# PMP30528_RevB.net
KiCad netlist of a schematic drawn in Altium Designer
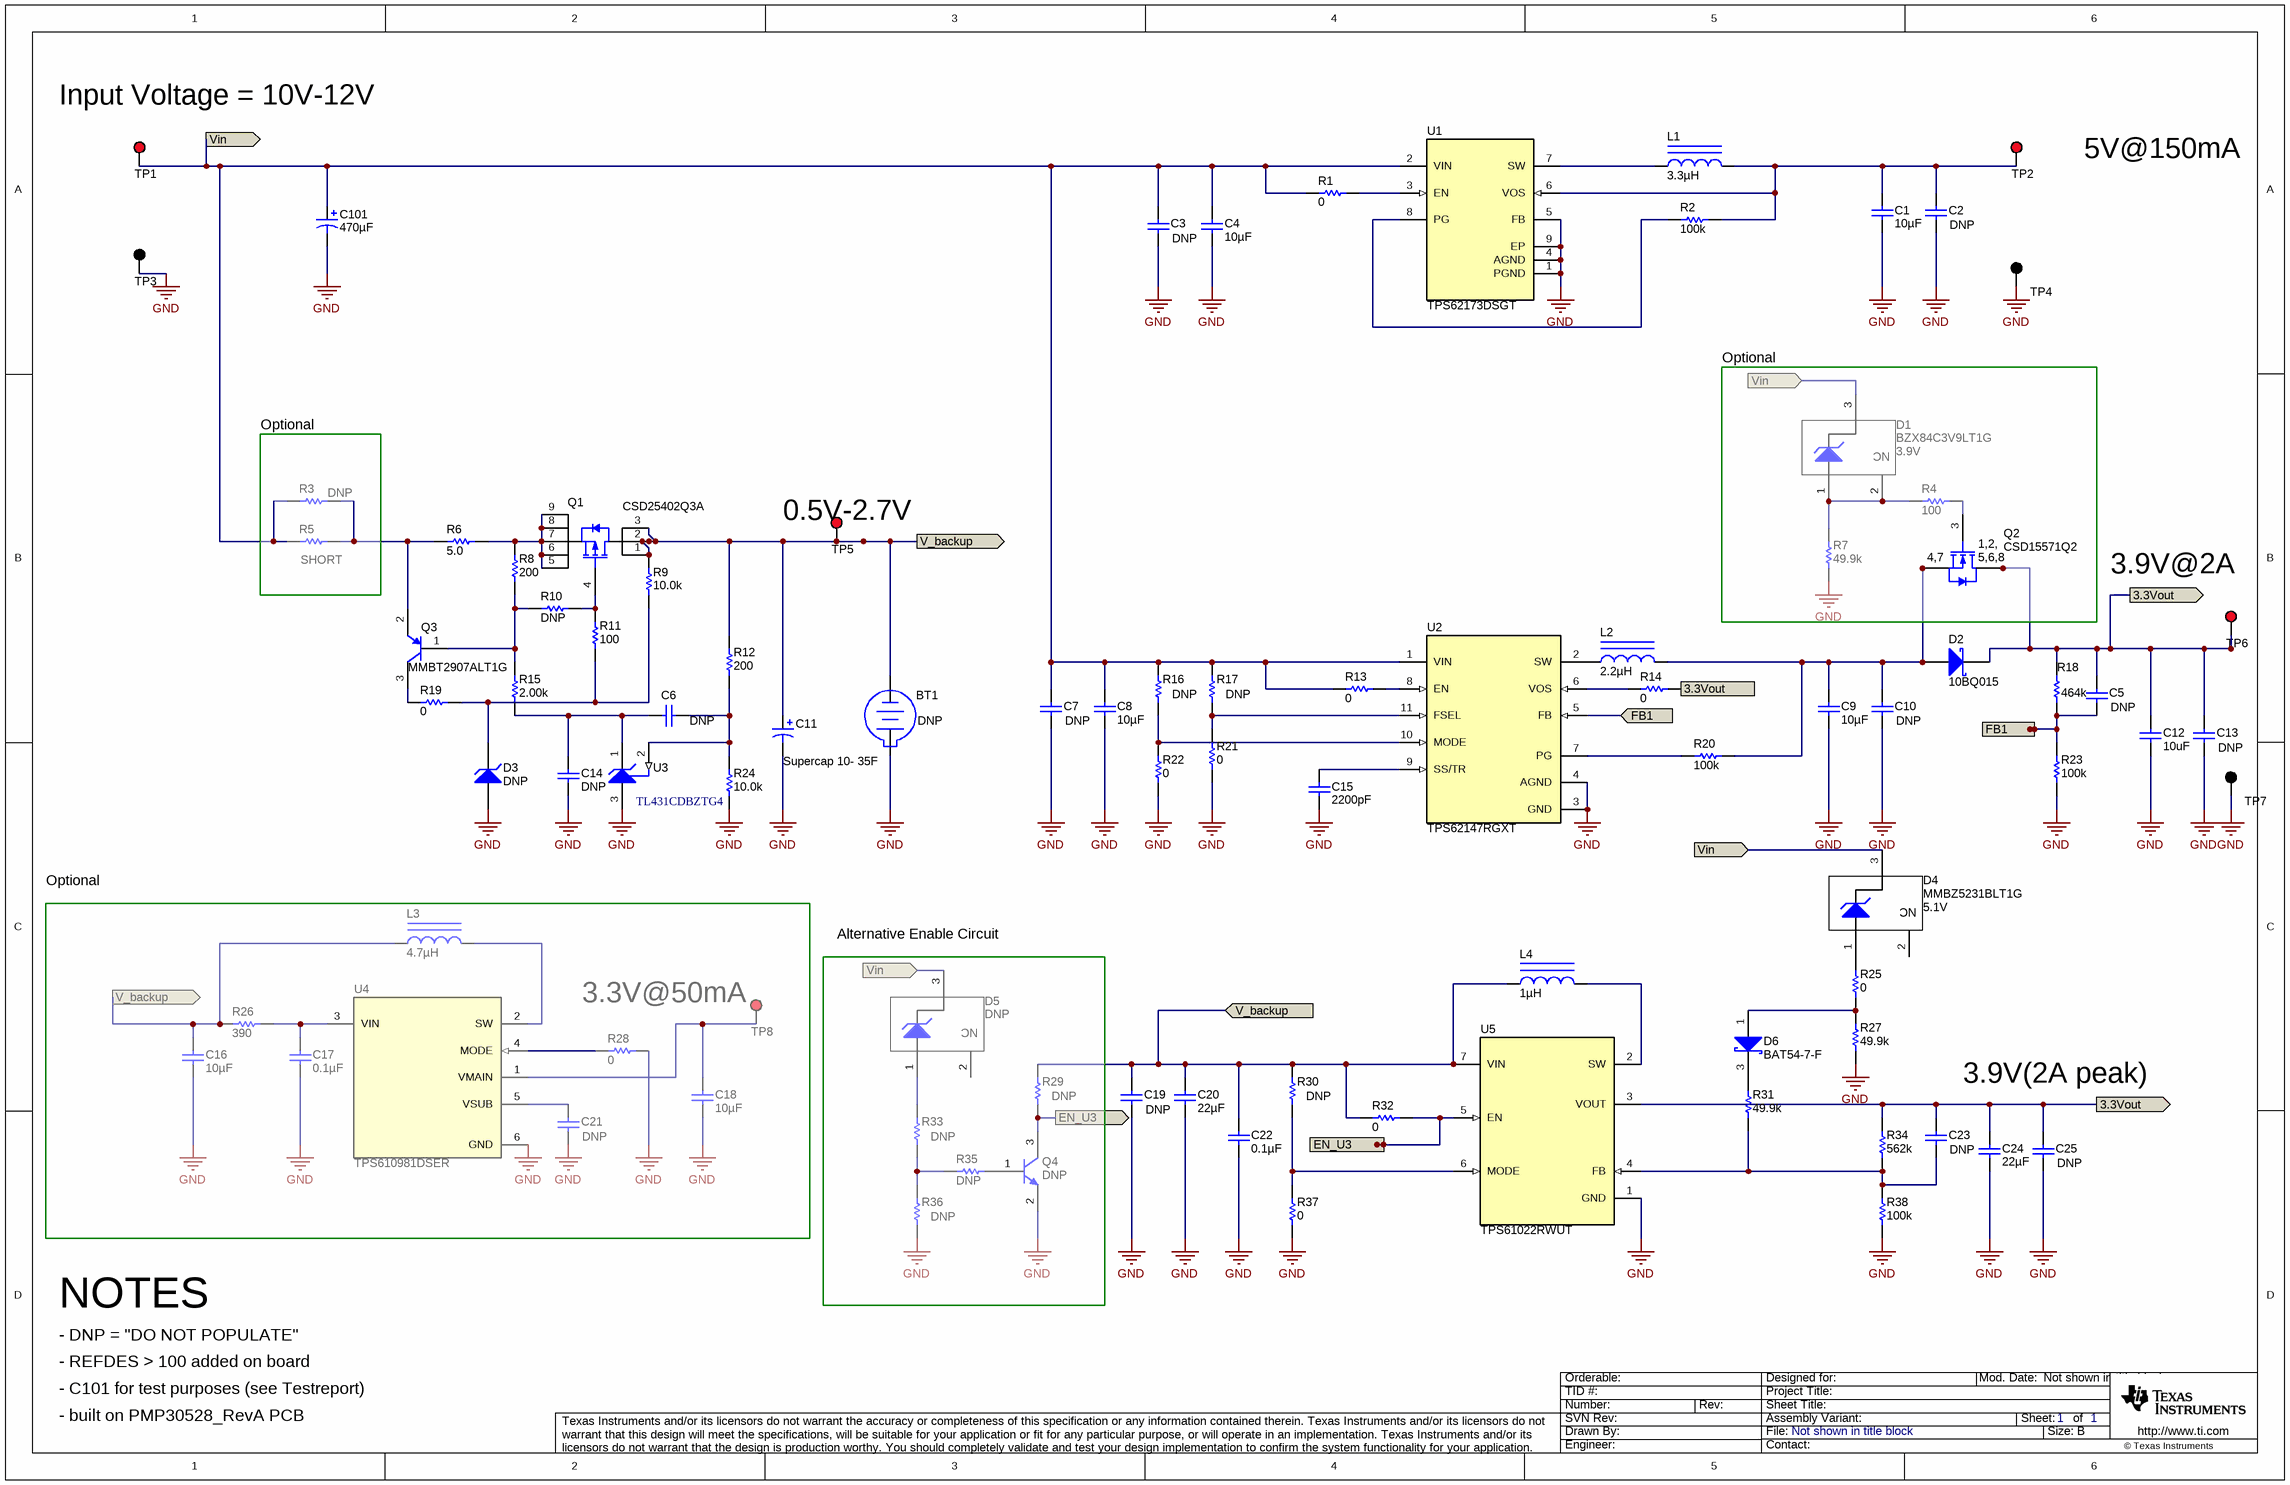
[diagram p0: PMP30528_RevB.SchDoc]

(export (version "E")
  (design (tool "Eeschema 10.0.6"))
  (components
    (comp (ref "BT1")
      (value "BU2032SM-BT-GTR")
      (footprint "MPD_BU2032SM-BT-GTR")
      (description "HOLDER CR2032 GOLD LEADS SMD")
      (fields (field (name "MANUFACTURER") "Memory Protection Devices") (field (name "PARTNUMBER") "DNP"))
      (libsource (lib "Altium Vault - TI") (part "BatteryHolder_Coin"))
    )
    (comp (ref "C1")
      (value "GRM21BR71A106KE51K")
      (footprint "0805_HV")
      (description "CAP, CERM, 10 µF, 10 V,+/- 10%, X7R, 0805")
      (fields
        (field (name "VALUEDISPLAYED") "10µF")
        (field (name "MANUFACTURER") "MuRata")
        (field (name "PUBLISHER") "Texas Instruments")
      )
      (libsource (lib "Capacitor_Ceramic") (part "GRM21BR71A106KE51K"))
    )
    (comp (ref "C2")
      (value "DNP")
      (footprint "0805")
      (description "CAP, CERM, xxxF, xxV, [TempCo], xx%, [PackageReference]")
      (fields
        (field (name "MANUFACTURER") "Used in BOM report")
        (field (name "PUBLISHER") "Texas Instruments")
      )
      (libsource (lib "MiscParts") (part "Capacitor"))
    )
    (comp (ref "C3")
      (value "DNP")
      (footprint "0805")
      (description "CAP, CERM, xxxF, xxV, [TempCo], xx%, [PackageReference]")
      (fields
        (field (name "MANUFACTURER") "Used in BOM report")
        (field (name "PUBLISHER") "Texas Instruments")
      )
      (libsource (lib "MiscParts") (part "Capacitor"))
    )
    (comp (ref "C4")
      (value "GRM21BZ71E106KE15L")
      (footprint "0805_HV")
      (description "CAP, CERM, 10 µF, 25 V,+/- 10%, X7R, 0805")
      (fields
        (field (name "VALUEDISPLAYED") "10µF")
        (field (name "MANUFACTURER") "MuRata")
        (field (name "PUBLISHER") "Texas Instruments")
      )
      (libsource (lib "Capacitor_Ceramic") (part "GRM21BZ71E106KE15L"))
    )
    (comp (ref "C5")
      (value "DNP")
      (footprint "0603")
      (description "CAP, CERM, xxxF, xxV, [TempCo], xx%, [PackageReference]")
      (fields
        (field (name "MANUFACTURER") "Used in BOM report")
        (field (name "PUBLISHER") "Texas Instruments")
      )
      (libsource (lib "MiscParts") (part "Capacitor"))
    )
    (comp (ref "C6")
      (value "DNP")
      (footprint "0805")
      (description "CAP, CERM, xxxF, xxV, [TempCo], xx%, [PackageReference]")
      (fields
        (field (name "MANUFACTURER") "Used in BOM report")
        (field (name "PUBLISHER") "Texas Instruments")
      )
      (libsource (lib "MiscParts") (part "Capacitor"))
    )
    (comp (ref "C7")
      (value "DNP")
      (footprint "0805")
      (description "CAP, CERM, xxxF, xxV, [TempCo], xx%, [PackageReference]")
      (fields
        (field (name "MANUFACTURER") "Used in BOM report")
        (field (name "PUBLISHER") "Texas Instruments")
      )
      (libsource (lib "MiscParts") (part "Capacitor"))
    )
    (comp (ref "C8")
      (value "GRM21BZ71E106KE15L")
      (footprint "0805")
      (description "CAP, CERM, 10 µF, 25 V,+/- 10%, X7R, 0805")
      (fields
        (field (name "VALUEDISPLAYED") "10µF")
        (field (name "MANUFACTURER") "MuRata")
        (field (name "PUBLISHER") "Texas Instruments")
      )
      (libsource (lib "Capacitor_Ceramic") (part "GRM21BZ71E106KE15L"))
    )
    (comp (ref "C9")
      (value "GRM31CR70J106KA01L")
      (footprint "1206_180")
      (description "CAP, CERM, 10 µF, 6.3 V,+/- 10%, X7R, 1206")
      (fields
        (field (name "VALUEDISPLAYED") "10µF")
        (field (name "MANUFACTURER") "MuRata")
        (field (name "PUBLISHER") "Texas Instruments")
      )
      (libsource (lib "Capacitor_Ceramic") (part "GRM31CR70J106KA01L"))
    )
    (comp (ref "C10")
      (value "DNP")
      (footprint "1206")
      (description "CAP, CERM, xxxF, xxV, [TempCo], xx%, [PackageReference]")
      (fields
        (field (name "MANUFACTURER") "Used in BOM report")
        (field (name "PUBLISHER") "Texas Instruments")
      )
      (libsource (lib "MiscParts") (part "Capacitor"))
    )
    (comp (ref "C11")
      (value "HV1625-2R7256-R")
      (footprint "HV_1600x2840")
      (description "CAP, Electric Double Layer, 25000000 µF, 2.7 V,+30/-10%, 0.027 ohm, TH")
      (fields (field (name "MANUFACTURER") "Eaton") (field (name "PARTNUMBER") "Supercap 10- 35F"))
      (libsource (lib "Altium Vault - TI") (part "CMP-0084049-1"))
    )
    (comp (ref "C12")
      (value "10uF")
      (footprint "1206")
      (description "CAP, CERM, 10 uF, 6.3 V, +/- 10%, X7R, 1206")
      (fields
        (field (name "MANUFACTURER") "TDK")
        (field (name "Comment") "C3216X7R1A106K085AC")
        (field (name "PUBLISHER") "Texas Instruments")
      )
      (libsource (lib "Altium Vault - TI") (part "CMP-0008687-2"))
    )
    (comp (ref "C13")
      (value "C3216X7R1A106K085AC")
      (footprint "1206")
      (description "CAP, CERM, 1206")
      (fields
        (field (name "MANUFACTURER") "TDK")
        (field (name "PARTNUMBER") "DNP")
        (field (name "PUBLISHER") "Texas Instruments")
      )
      (libsource (lib "Altium Vault - TI") (part "CMP-0008687-2"))
    )
    (comp (ref "C14")
      (value "DNP")
      (footprint "0805")
      (description "CAP, CERM, xxxF, xxV, [TempCo], xx%, [PackageReference]")
      (fields
        (field (name "MANUFACTURER") "Used in BOM report")
        (field (name "PUBLISHER") "Texas Instruments")
      )
      (libsource (lib "MiscParts") (part "Capacitor"))
    )
    (comp (ref "C15")
      (value "C0603X222K5RACTU")
      (footprint "0603")
      (description "CAP, CERM, 2200 pF, 50 V,+/- 10%, X7R, 0603")
      (fields
        (field (name "VALUEDISPLAYED") "2200pF")
        (field (name "MANUFACTURER") "Kemet")
        (field (name "PUBLISHER") "Texas Instruments")
      )
      (libsource (lib "Capacitor_Ceramic") (part "C0603X222K5RACTU"))
    )
    (comp (ref "C16")
      (value "GRM21BR70J106KE76L")
      (footprint "0805_HV")
      (description "CAP, CERM, 10 µF, 6.3 V,+/- 10%, X7R, 0805")
      (fields
        (field (name "VALUEDISPLAYED") "10µF")
        (field (name "MANUFACTURER") "MuRata")
        (field (name "PUBLISHER") "Texas Instruments")
      )
      (libsource (lib "Capacitor_Ceramic") (part "GRM21BR70J106KE76L"))
    )
    (comp (ref "C17")
      (value "GRM21BR71H104KA01L")
      (footprint "0805_HV")
      (description "CAP, CERM, 0.1 µF, 50 V,+/- 10%, X7R, 0805")
      (fields
        (field (name "VALUEDISPLAYED") "0.1µF")
        (field (name "MANUFACTURER") "MuRata")
        (field (name "PUBLISHER") "Texas Instruments")
      )
      (libsource (lib "Capacitor_Ceramic") (part "GRM21BR71H104KA01L"))
    )
    (comp (ref "C18")
      (value "GRM21BR70J106KE76L")
      (footprint "0805_HV")
      (description "CAP, CERM, 10 µF, 6.3 V,+/- 10%, X7R, 0805")
      (fields
        (field (name "VALUEDISPLAYED") "10µF")
        (field (name "MANUFACTURER") "MuRata")
        (field (name "PUBLISHER") "Texas Instruments")
      )
      (libsource (lib "Capacitor_Ceramic") (part "GRM21BR70J106KE76L"))
    )
    (comp (ref "C19")
      (value "DNP")
      (footprint "0805")
      (description "CAP, CERM, xxxF, xxV, [TempCo], xx%, [PackageReference]")
      (fields
        (field (name "MANUFACTURER") "Used in BOM report")
        (field (name "PUBLISHER") "Texas Instruments")
      )
      (libsource (lib "MiscParts") (part "Capacitor"))
    )
    (comp (ref "C20")
      (value "GRM31CR70J226KE19L")
      (footprint "1206_180")
      (description "CAP, CERM, 22 µF, 6.3 V,+/- 10%, X7R, 1206")
      (fields
        (field (name "VALUEDISPLAYED") "22µF")
        (field (name "MANUFACTURER") "MuRata")
        (field (name "PUBLISHER") "Texas Instruments")
      )
      (libsource (lib "Capacitor_Ceramic") (part "GRM31CR70J226KE19L"))
    )
    (comp (ref "C21")
      (value "DNP")
      (footprint "0805")
      (description "CAP, CERM, xxxF, xxV, [TempCo], xx%, [PackageReference]")
      (fields
        (field (name "MANUFACTURER") "Used in BOM report")
        (field (name "PUBLISHER") "Texas Instruments")
      )
      (libsource (lib "MiscParts") (part "Capacitor"))
    )
    (comp (ref "C22")
      (value "GRM188R71H104KA93D")
      (footprint "0603")
      (description "CAP, CERM, 0.1 µF, 50 V,+/- 10%, X7R, 0603")
      (fields
        (field (name "VALUEDISPLAYED") "0.1µF")
        (field (name "MANUFACTURER") "MuRata")
        (field (name "PUBLISHER") "Texas Instruments")
      )
      (libsource (lib "Capacitor_Ceramic") (part "GRM188R71H104KA93D"))
    )
    (comp (ref "C23")
      (value "DNP")
      (footprint "0603")
      (description "CAP, CERM, xxxF, xxV, [TempCo], xx%, [PackageReference]")
      (fields
        (field (name "MANUFACTURER") "Used in BOM report")
        (field (name "PUBLISHER") "Texas Instruments")
      )
      (libsource (lib "MiscParts") (part "Capacitor"))
    )
    (comp (ref "C24")
      (value "GRM31CR71A226ME15L")
      (footprint "1206_180")
      (description "CAP, CERM, 22 µF, 10 V,+/- 20%, X7R, 1206")
      (fields
        (field (name "VALUEDISPLAYED") "22µF")
        (field (name "MANUFACTURER") "MuRata")
        (field (name "PUBLISHER") "Texas Instruments")
      )
      (libsource (lib "Capacitor_Ceramic") (part "GRM31CR71A226ME15L"))
    )
    (comp (ref "C25")
      (value "DNP")
      (footprint "1206")
      (description "CAP, CERM, xxxF, xxV, [TempCo], xx%, [PackageReference]")
      (fields
        (field (name "MANUFACTURER") "Used in BOM report")
        (field (name "PUBLISHER") "Texas Instruments")
      )
      (libsource (lib "MiscParts") (part "Capacitor"))
    )
    (comp (ref "C101")
      (value "EKZE350ELL471MJ20S")
      (footprint "Chemi-Con_1000x2000")
      (description "CAP, AL, 470 µF, 35 V, +/- 20%, TH")
      (fields
        (field (name "VALUEDISPLAYED") "470µF")
        (field (name "MANUFACTURER") "Chemi-Con")
        (field (name "PUBLISHER") "Texas Instruments")
      )
      (libsource (lib "Capacitor_Aluminum") (part "EKZE350ELL471MJ20S"))
    )
    (comp (ref "D1")
      (value "BZX84C3V9LT1G")
      (footprint "SOT-23")
      (description "Diode, Zener, 3.9 V, 225 mW, SOT-23")
      (fields
        (field (name "MANUFACTURER") "ON Semiconductor")
        (field (name "ALTIUM_VALUE") "3.9V")
        (field (name "PUBLISHER") "Texas Instruments")
      )
      (libsource (lib "ZenerDiodes") (part "BZX84C3V9LT1G"))
    )
    (comp (ref "D2")
      (value "10BQ015")
      (footprint "SMB")
      (description "Diode, Schottky, 15 V, 1 A, SMB")
      (fields
        (field (name "MANUFACTURER") "Vishay-Semiconductor")
        (field (name "PUBLISHER") "Texas Instruments")
      )
      (libsource (lib "Diode") (part "VS-10BQ030HM3/5BT"))
    )
    (comp (ref "D3")
      (value "DNP")
      (footprint "SOD-523")
      (description "Diode, Zener")
      (fields
        (field (name "MANUFACTURER") "Diodes Inc.")
        (field (name "SYMBOLCREATOR") "a0412235")
        (field (name "PUBLISHER") "Texas Instruments")
      )
      (libsource (lib "ZenerDiodes") (part "BZT52C2V7T-7"))
    )
    (comp (ref "D4")
      (value "MMBZ5231BLT1G")
      (footprint "SOT-23")
      (description "Diode, Zener, 5.1 V, 225 mW, SOT-23")
      (fields
        (field (name "MANUFACTURER") "ON Semiconductor")
        (field (name "ALTIUM_VALUE") "5.1V")
        (field (name "PUBLISHER") "Texas Instruments")
      )
      (libsource (lib "ZenerDiodes") (part "MMBZ5231BLT1G"))
    )
    (comp (ref "D5")
      (value "DNP")
      (footprint "SOT-23")
      (description "Diode, Zener")
      (fields (field (name "MANUFACTURER") "ON Semiconductor") (field (name "PUBLISHER") "Texas Instruments"))
      (libsource (lib "ZenerDiodes") (part "MMBZ5231BLT1G"))
    )
    (comp (ref "D6")
      (value "BAT54-7-F")
      (footprint "SOT-23")
      (description "Diode, Schottky, 30 V, 0.2 A, SOT-23")
      (fields (field (name "MANUFACTURER") "Diodes Inc.") (field (name "PUBLISHER") "Texas Instruments"))
      (libsource (lib "Diode") (part "BAT54-7-F"))
    )
    (comp (ref "L1")
      (value "LPS3015-332MLB")
      (footprint "LPS3015")
      (description "Inductor, Shielded Drum Core, Ferrite, 3.3 µH, 1.4 A, 0.13 ohm, SMD")
      (fields
        (field (name "VALUEDISPLAYED") "3.3µH")
        (field (name "MANUFACTURER") "Coilcraft")
        (field (name "PUBLISHER") "Texas Instruments")
      )
      (libsource (lib "Inductor_Coilcraft") (part "LPS3015-332MLB"))
    )
    (comp (ref "L2")
      (value "XFL4020-222MEB")
      (footprint "XFL4020")
      (description "Inductor, Shielded, Composite, 2.2 µH, 3.7 A, 0.02 ohm, SMD")
      (fields
        (field (name "VALUEDISPLAYED") "2.2µH")
        (field (name "MANUFACTURER") "Coilcraft")
        (field (name "PUBLISHER") "Texas Instruments")
      )
      (libsource (lib "Inductor_Coilcraft") (part "XFL4020-222MEB"))
    )
    (comp (ref "L3")
      (value "VLF302510MT-4R7M")
      (footprint "VLF302510MT")
      (description "Inductor, Shielded, Ferrite, 4.7 µH, 0.86 A, 0.168 ohm, SMD")
      (fields
        (field (name "VALUEDISPLAYED") "4.7µH")
        (field (name "MANUFACTURER") "TDK")
        (field (name "PUBLISHER") "Texas Instruments")
      )
      (libsource (lib "Inductor_TDK") (part "VLF302510MT-4R7M"))
    )
    (comp (ref "L4")
      (value "XAL6030-102MEB")
      (footprint "XAL6030")
      (description "Inductor, Shielded, Composite, 1 µH, 21.5 A, 0.01 ohm, SMD")
      (fields
        (field (name "VALUEDISPLAYED") "1µH")
        (field (name "MANUFACTURER") "Coilcraft")
        (field (name "PUBLISHER") "Texas Instruments")
      )
      (libsource (lib "Inductor_Coilcraft") (part "XAL6030-102MEB"))
    )
    (comp (ref "Q1")
      (value "CSD25402Q3A")
      (footprint "DNH0008A")
      (description "MOSFET, P-CH, -20 V, -15 A, DNH0008A (VSONP-8)")
      (fields
        (field (name "MANUFACTURER") "Texas Instruments")
        (field (name "SYMBOLCREATOR") "a0799628")
        (field (name "PUBLISHER") "Texas Instruments")
      )
      (libsource (lib "FETs") (part "CSD25402Q3A"))
    )
    (comp (ref "Q2")
      (value "CSD15571Q2")
      (footprint "DQK0006C")
      (description "MOSFET, N-CH, 20 V, 10 A, DQK0006C (WSON-6)")
      (fields
        (field (name "MANUFACTURER") "Texas Instruments")
        (field (name "PUBLISHER") "Texas Instruments")
      )
      (libsource (lib "Altium Vault - TI") (part "MOSFET_N_D12568G3S47"))
    )
    (comp (ref "Q3")
      (value "MMBT2907ALT1G")
      (footprint "SOT-23")
      (description "Transistor, PNP, 60 V, 0.6 A, SOT-23")
      (fields (field (name "MANUFACTURER") "ON Semiconductor") (field (name "PUBLISHER") "Texas Instruments"))
      (libsource (lib "Bipolar_Transistor") (part "MMBT2907ALT1G, ON Semiconductor"))
    )
    (comp (ref "Q4")
      (value "DNP")
      (footprint "SOT-23")
      (description "Transistor, NPN, 40 V, 0.2 A, SOT-23")
      (fields
        (field (name "MANUFACTURER") "Fairchild Semiconductor")
        (field (name "PUBLISHER") "Texas Instruments")
      )
      (libsource (lib "Bipolar_Transistor") (part "MMBT3904, Fairchild Semiconductor"))
    )
    (comp (ref "R1")
      (value "CRCW06030000Z0EA")
      (footprint "0603")
      (description "RES, 0, 5%, 0.1 W, 0603")
      (fields
        (field (name "VALUEDISPLAYED") "0")
        (field (name "MANUFACTURER") "Vishay-Dale")
        (field (name "PUBLISHER") "Texas Instruments")
      )
      (libsource (lib "Resistor_0603") (part "CRCW06030000Z0EA"))
    )
    (comp (ref "R2")
      (value "CRCW0603100KFKEA")
      (footprint "0603")
      (description "RES, 100 k, 1%, 0.1 W, 0603")
      (fields
        (field (name "VALUEDISPLAYED") "100k")
        (field (name "MANUFACTURER") "Vishay-Dale")
        (field (name "PUBLISHER") "Texas Instruments")
      )
      (libsource (lib "Resistor_0603") (part "CRCW0603100KFKEA"))
    )
    (comp (ref "R3")
      (value "DNP")
      (footprint "PNP300")
      (description "RES, 47, 5%, 3 W, 3W Axial resistor")
      (fields
        (field (name "PARTNUMBER") "PNP300JR-73-47R")
        (field (name "MANUFACTURER") "Yageo America")
        (field (name "PUBLISHER") "Texas Instruments")
      )
      (libsource (lib "Resistor_TH") (part "PNP300JR-73-47R"))
    )
    (comp (ref "R4")
      (value "CRCW0805100RFKEA")
      (footprint "0805_HV")
      (description "RES, 100, 1%, 0.125 W, 0805")
      (fields
        (field (name "VALUEDISPLAYED") "100")
        (field (name "MANUFACTURER") "Vishay-Dale")
        (field (name "PUBLISHER") "Texas Instruments")
      )
      (libsource (lib "Resistor_0805") (part "CRCW0805100RFKEA"))
    )
    (comp (ref "R5")
      (value "SHORT")
      (footprint "PNP300")
      (description "RES, 3 W, 3W Axial resistor")
      (fields (field (name "MANUFACTURER") "Yageo America") (field (name "PUBLISHER") "Texas Instruments"))
      (libsource (lib "Resistor_TH") (part "PNP300JR-73-47R"))
    )
    (comp (ref "R6")
      (value "RC1206FR")
      (footprint "1206")
      (description "RES, 5.0ohm, 1%, 0.25 W, 1206")
      (fields
        (field (name "MANUFACTURER") "Yageo America")
        (field (name "PARTNUMBER") "RC1206FR-071R96L")
        (field (name "VALUEDISPLAYED") "5.0")
        (field (name "PUBLISHER") "Texas Instruments")
      )
      (libsource (lib "Altium Vault - TI") (part "Resistor"))
    )
    (comp (ref "R7")
      (value "CRCW080549K9FKEA")
      (footprint "0805_HV")
      (description "RES, 49.9 k, 1%, 0.125 W, 0805")
      (fields
        (field (name "VALUEDISPLAYED") "49.9k")
        (field (name "MANUFACTURER") "Vishay-Dale")
        (field (name "PUBLISHER") "Texas Instruments")
      )
      (libsource (lib "Resistor_0805") (part "CRCW080549K9FKEA"))
    )
    (comp (ref "R8")
      (value "CRCW0603200RFKEA")
      (footprint "0603")
      (description "RES, 200, 1%, 0.1 W, 0603")
      (fields
        (field (name "VALUEDISPLAYED") "200")
        (field (name "MANUFACTURER") "Vishay-Dale")
        (field (name "PUBLISHER") "Texas Instruments")
      )
      (libsource (lib "Resistor_0603") (part "CRCW0603200RFKEA"))
    )
    (comp (ref "R9")
      (value "CRCW060310K0FKEA")
      (footprint "0603")
      (description "RES, 10.0 k, 1%, 0.1 W, 0603")
      (fields
        (field (name "VALUEDISPLAYED") "10.0k")
        (field (name "MANUFACTURER") "Vishay-Dale")
        (field (name "PUBLISHER") "Texas Instruments")
      )
      (libsource (lib "Resistor_0603") (part "CRCW060310K0FKEA"))
    )
    (comp (ref "R10")
      (value "DNP")
      (footprint "0603")
      (description "RES, xxx ohm, x%, xW, [PackageReference]")
      (fields
        (field (name "MANUFACTURER") "Used in BOM report")
        (field (name "PUBLISHER") "Texas Instruments")
      )
      (libsource (lib "MiscParts") (part "Resistor"))
    )
    (comp (ref "R11")
      (value "CRCW0805100RFKEA")
      (footprint "0805_HV")
      (description "RES, 100, 1%, 0.125 W, 0805")
      (fields
        (field (name "VALUEDISPLAYED") "100")
        (field (name "MANUFACTURER") "Vishay-Dale")
        (field (name "PUBLISHER") "Texas Instruments")
      )
      (libsource (lib "Resistor_0805") (part "CRCW0805100RFKEA"))
    )
    (comp (ref "R12")
      (value "CRCW0603200RFKEA")
      (footprint "0603")
      (description "RES, 200, 1%, 0.1 W, 0603")
      (fields
        (field (name "VALUEDISPLAYED") "200")
        (field (name "MANUFACTURER") "Vishay-Dale")
        (field (name "PUBLISHER") "Texas Instruments")
      )
      (libsource (lib "Resistor_0603") (part "CRCW0603200RFKEA"))
    )
    (comp (ref "R13")
      (value "CRCW06030000Z0EA")
      (footprint "0603")
      (description "RES, 0, 5%, 0.1 W, 0603")
      (fields
        (field (name "VALUEDISPLAYED") "0")
        (field (name "MANUFACTURER") "Vishay-Dale")
        (field (name "PUBLISHER") "Texas Instruments")
      )
      (libsource (lib "Resistor_0603") (part "CRCW06030000Z0EA"))
    )
    (comp (ref "R14")
      (value "CRCW06030000Z0EA")
      (footprint "0603")
      (description "RES, 0, 5%, 0.1 W, 0603")
      (fields
        (field (name "VALUEDISPLAYED") "0")
        (field (name "MANUFACTURER") "Vishay-Dale")
        (field (name "PUBLISHER") "Texas Instruments")
      )
      (libsource (lib "Resistor_0603") (part "CRCW06030000Z0EA"))
    )
    (comp (ref "R15")
      (value "CRCW06032K00FKEA")
      (footprint "0603")
      (description "RES, 2.00 k, 1%, 0.1 W, 0603")
      (fields
        (field (name "VALUEDISPLAYED") "2.00k")
        (field (name "MANUFACTURER") "Vishay-Dale")
        (field (name "PUBLISHER") "Texas Instruments")
      )
      (libsource (lib "Resistor_0603") (part "CRCW06032K00FKEA"))
    )
    (comp (ref "R16")
      (value "DNP")
      (footprint "0603_HV")
      (description "RES, xxx ohm, x%, xW, [PackageReference]")
      (fields
        (field (name "MANUFACTURER") "Used in BOM report")
        (field (name "PUBLISHER") "Texas Instruments")
      )
      (libsource (lib "MiscParts") (part "Resistor"))
    )
    (comp (ref "R17")
      (value "DNP")
      (footprint "0603_HV")
      (description "RES, xxx ohm, x%, xW, [PackageReference]")
      (fields
        (field (name "MANUFACTURER") "Used in BOM report")
        (field (name "PUBLISHER") "Texas Instruments")
      )
      (libsource (lib "MiscParts") (part "Resistor"))
    )
    (comp (ref "R18")
      (value "CRCW0603464KFKEA")
      (footprint "0603")
      (description "RES, 464 k, 1%, 0.1 W, 0603")
      (fields
        (field (name "VALUEDISPLAYED") "464k")
        (field (name "MANUFACTURER") "Vishay-Dale")
        (field (name "PUBLISHER") "Texas Instruments")
      )
      (libsource (lib "Resistor_0603") (part "CRCW0603464KFKEA"))
    )
    (comp (ref "R19")
      (value "CRCW06030000Z0EA")
      (footprint "0603")
      (description "RES, 0, 5%, 0.1 W, 0603")
      (fields
        (field (name "VALUEDISPLAYED") "0")
        (field (name "MANUFACTURER") "Vishay-Dale")
        (field (name "PUBLISHER") "Texas Instruments")
      )
      (libsource (lib "Resistor_0603") (part "CRCW06030000Z0EA"))
    )
    (comp (ref "R20")
      (value "CRCW0603100KFKEA")
      (footprint "0603")
      (description "RES, 100 k, 1%, 0.1 W, 0603")
      (fields
        (field (name "VALUEDISPLAYED") "100k")
        (field (name "MANUFACTURER") "Vishay-Dale")
        (field (name "PUBLISHER") "Texas Instruments")
      )
      (libsource (lib "Resistor_0603") (part "CRCW0603100KFKEA"))
    )
    (comp (ref "R21")
      (value "RC0603JR-070RL")
      (footprint "0603")
      (description "RES, 0, 5%, 0.1 W, 0603")
      (fields
        (field (name "VALUEDISPLAYED") "0")
        (field (name "MANUFACTURER") "Yageo America")
        (field (name "PUBLISHER") "Texas Instruments")
      )
      (libsource (lib "Resistor_0603") (part "RC0603JR-070RL"))
    )
    (comp (ref "R22")
      (value "RC0603JR-070RL")
      (footprint "0603")
      (description "RES, 0, 5%, 0.1 W, 0603")
      (fields
        (field (name "VALUEDISPLAYED") "0")
        (field (name "MANUFACTURER") "Yageo America")
        (field (name "PUBLISHER") "Texas Instruments")
      )
      (libsource (lib "Resistor_0603") (part "RC0603JR-070RL"))
    )
    (comp (ref "R23")
      (value "CRCW0603100KFKEA")
      (footprint "0603")
      (description "RES, 100 k, 1%, 0.1 W, 0603")
      (fields
        (field (name "VALUEDISPLAYED") "100k")
        (field (name "MANUFACTURER") "Vishay-Dale")
        (field (name "PUBLISHER") "Texas Instruments")
      )
      (libsource (lib "Resistor_0603") (part "CRCW0603100KFKEA"))
    )
    (comp (ref "R24")
      (value "CRCW060310K0FKEA")
      (footprint "0603")
      (description "RES, 10.0 k, 1%, 0.1 W, 0603")
      (fields
        (field (name "VALUEDISPLAYED") "10.0k")
        (field (name "MANUFACTURER") "Vishay-Dale")
        (field (name "PUBLISHER") "Texas Instruments")
      )
      (libsource (lib "Resistor_0603") (part "CRCW060310K0FKEA"))
    )
    (comp (ref "R25")
      (value "CRCW06030000Z0EA")
      (footprint "0603")
      (description "RES, 0, 5%, 0.1 W, 0603")
      (fields
        (field (name "VALUEDISPLAYED") "0")
        (field (name "MANUFACTURER") "Vishay-Dale")
        (field (name "PUBLISHER") "Texas Instruments")
      )
      (libsource (lib "Resistor_0603") (part "CRCW06030000Z0EA"))
    )
    (comp (ref "R26")
      (value "CRCW0805390RJNEA")
      (footprint "0805_HV")
      (description "RES, 390, 5%, 0.125 W, 0805")
      (fields
        (field (name "VALUEDISPLAYED") "390")
        (field (name "MANUFACTURER") "Vishay-Dale")
        (field (name "PUBLISHER") "Texas Instruments")
      )
      (libsource (lib "Resistor_0805") (part "CRCW0805390RJNEA"))
    )
    (comp (ref "R27")
      (value "CRCW080549K9FKEA")
      (footprint "0805_HV")
      (description "RES, 49.9 k, 1%, 0.125 W, 0805")
      (fields
        (field (name "VALUEDISPLAYED") "49.9k")
        (field (name "MANUFACTURER") "Vishay-Dale")
        (field (name "PUBLISHER") "Texas Instruments")
      )
      (libsource (lib "Resistor_0805") (part "CRCW080549K9FKEA"))
    )
    (comp (ref "R28")
      (value "CRCW06030000Z0EA")
      (footprint "0603")
      (description "RES, 0, 5%, 0.1 W, 0603")
      (fields
        (field (name "VALUEDISPLAYED") "0")
        (field (name "MANUFACTURER") "Vishay-Dale")
        (field (name "PUBLISHER") "Texas Instruments")
      )
      (libsource (lib "Resistor_0603") (part "CRCW06030000Z0EA"))
    )
    (comp (ref "R29")
      (value "DNP")
      (footprint "0603")
      (description "RES, xxx ohm, x%, xW, [PackageReference]")
      (fields
        (field (name "MANUFACTURER") "Used in BOM report")
        (field (name "PUBLISHER") "Texas Instruments")
      )
      (libsource (lib "MiscParts") (part "Resistor"))
    )
    (comp (ref "R30")
      (value "DNP")
      (footprint "0603")
      (description "RES, xxx ohm, x%, xW, [PackageReference]")
      (fields
        (field (name "MANUFACTURER") "Used in BOM report")
        (field (name "PUBLISHER") "Texas Instruments")
      )
      (libsource (lib "MiscParts") (part "Resistor"))
    )
    (comp (ref "R31")
      (value "CRCW080549K9FKEA")
      (footprint "0805_HV")
      (description "RES, 49.9 k, 1%, 0.125 W, 0805")
      (fields
        (field (name "VALUEDISPLAYED") "49.9k")
        (field (name "MANUFACTURER") "Vishay-Dale")
        (field (name "PUBLISHER") "Texas Instruments")
      )
      (libsource (lib "Resistor_0805") (part "CRCW080549K9FKEA"))
    )
    (comp (ref "R32")
      (value "CRCW06030000Z0EA")
      (footprint "0603")
      (description "RES, 0, 5%, 0.1 W, 0603")
      (fields
        (field (name "VALUEDISPLAYED") "0")
        (field (name "MANUFACTURER") "Vishay-Dale")
        (field (name "PUBLISHER") "Texas Instruments")
      )
      (libsource (lib "Resistor_0603") (part "CRCW06030000Z0EA"))
    )
    (comp (ref "R33")
      (value "DNP")
      (footprint "0603")
      (description "RES, xxx ohm, x%, xW, [PackageReference]")
      (fields
        (field (name "MANUFACTURER") "Used in BOM report")
        (field (name "PUBLISHER") "Texas Instruments")
      )
      (libsource (lib "MiscParts") (part "Resistor"))
    )
    (comp (ref "R34")
      (value "CRCW0603562KFKEA")
      (footprint "0603")
      (description "RES, 562 k, 1%, 0.1 W, 0603")
      (fields
        (field (name "VALUEDISPLAYED") "562k")
        (field (name "MANUFACTURER") "Vishay-Dale")
        (field (name "PUBLISHER") "Texas Instruments")
      )
      (libsource (lib "Resistor_0603") (part "CRCW0603562KFKEA"))
    )
    (comp (ref "R35")
      (value "DNP")
      (footprint "0603")
      (description "RES, xxx ohm, x%, xW, [PackageReference]")
      (fields
        (field (name "MANUFACTURER") "Used in BOM report")
        (field (name "PUBLISHER") "Texas Instruments")
      )
      (libsource (lib "MiscParts") (part "Resistor"))
    )
    (comp (ref "R36")
      (value "DNP")
      (footprint "0603")
      (description "RES, xxx ohm, x%, xW, [PackageReference]")
      (fields
        (field (name "MANUFACTURER") "Used in BOM report")
        (field (name "PUBLISHER") "Texas Instruments")
      )
      (libsource (lib "MiscParts") (part "Resistor"))
    )
    (comp (ref "R37")
      (value "CRCW06030000Z0EA")
      (footprint "0603")
      (description "RES, 0, 5%, 0.1 W, 0603")
      (fields
        (field (name "VALUEDISPLAYED") "0")
        (field (name "MANUFACTURER") "Vishay-Dale")
        (field (name "PUBLISHER") "Texas Instruments")
      )
      (libsource (lib "Resistor_0603") (part "CRCW06030000Z0EA"))
    )
    (comp (ref "R38")
      (value "CRCW0603100KFKEA")
      (footprint "0603")
      (description "RES, 100 k, 1%, 0.1 W, 0603")
      (fields
        (field (name "VALUEDISPLAYED") "100k")
        (field (name "MANUFACTURER") "Vishay-Dale")
        (field (name "PUBLISHER") "Texas Instruments")
      )
      (libsource (lib "Resistor_0603") (part "CRCW0603100KFKEA"))
    )
    (comp (ref "TP1")
      (value "5000")
      (footprint "Keystone5000")
      (description "Test Point, Miniature, Red, TH")
      (fields (field (name "MANUFACTURER") "Keystone") (field (name "PUBLISHER") "Texas Instruments"))
      (libsource (lib "Connectors_Keystone") (part "5000"))
    )
    (comp (ref "TP2")
      (value "5000")
      (footprint "Keystone5000")
      (description "Test Point, Miniature, Red, TH")
      (fields (field (name "MANUFACTURER") "Keystone") (field (name "PUBLISHER") "Texas Instruments"))
      (libsource (lib "Connectors_Keystone") (part "5000"))
    )
    (comp (ref "TP3")
      (value "5001")
      (footprint "Keystone5001")
      (description "Test Point, Miniature, Black, TH")
      (fields (field (name "MANUFACTURER") "Keystone") (field (name "PUBLISHER") "Texas Instruments"))
      (libsource (lib "Connectors_Keystone") (part "5001"))
    )
    (comp (ref "TP4")
      (value "5001")
      (footprint "Keystone5001")
      (description "Test Point, Miniature, Black, TH")
      (fields (field (name "MANUFACTURER") "Keystone") (field (name "PUBLISHER") "Texas Instruments"))
      (libsource (lib "Connectors_Keystone") (part "5001"))
    )
    (comp (ref "TP5")
      (value "5000")
      (footprint "Keystone5000")
      (description "Test Point, Miniature, Red, TH")
      (fields (field (name "MANUFACTURER") "Keystone") (field (name "PUBLISHER") "Texas Instruments"))
      (libsource (lib "Connectors_Keystone") (part "5000"))
    )
    (comp (ref "TP6")
      (value "5000")
      (footprint "Keystone5000")
      (description "Test Point, Miniature, Red, TH")
      (fields (field (name "MANUFACTURER") "Keystone") (field (name "PUBLISHER") "Texas Instruments"))
      (libsource (lib "Connectors_Keystone") (part "5000"))
    )
    (comp (ref "TP7")
      (value "5001")
      (footprint "Keystone5001")
      (description "Test Point, Miniature, Black, TH")
      (fields (field (name "MANUFACTURER") "Keystone") (field (name "PUBLISHER") "Texas Instruments"))
      (libsource (lib "Connectors_Keystone") (part "5001"))
    )
    (comp (ref "TP8")
      (value "5000")
      (footprint "Keystone5000")
      (description "Test Point, Miniature, Red, TH")
      (fields (field (name "MANUFACTURER") "Keystone") (field (name "PUBLISHER") "Texas Instruments"))
      (libsource (lib "Connectors_Keystone") (part "5000"))
    )
    (comp (ref "U1")
      (value "TPS62173DSGT")
      (footprint "DSG0008A")
      (fields (field (name "MANUFACTURER") "Texas Instruments") (field (name "PARTNUMBER") "TPS62173DSGT"))
      (libsource (lib "Altium Vault - TI") (part "CMP-0037800-2"))
    )
    (comp (ref "U2")
      (value "TPS62147RGXT")
      (footprint "RGX0011A")
      (fields
        (field (name "ALTERNATE PARTNUMBER") "TPS62147RGXR")
        (field (name "MANUFACTURER") "Texas Instruments")
        (field (name "PARTNUMBER") "TPS62147RGXT")
      )
      (libsource (lib "Altium Vault - TI") (part "TPS62148"))
    )
    (comp (ref "U3")
      (value "TL431CDBZTG4")
      (footprint "DBZ0003A_N")
      (fields
        (field (name "MANUFACTURER") "Texas Instruments")
        (field (name "ALTERNATE PARTNUMBER") "Equivalent")
      )
      (libsource (lib "TI Power Management Shunt Voltage Reference") (part "TL431CDBZTG4"))
    )
    (comp (ref "U4")
      (value "TPS610981DSER")
      (footprint "DSE0006A")
      (description "Low Input Voltage Synchronous Boost Converter with Integrated LDO/Load Switch, DSE0006A (WSON-6)")
      (fields
        (field (name "ALTERNATE PARTNUMBER") "TPS610981DSET")
        (field (name "MANUFACTURER") "Texas Instruments")
        (field (name "SYMBOLCREATOR") "Altium")
        (field (name "PUBLISHER") "Texas Instruments")
      )
      (libsource (lib "TI_Pre_Release1") (part "TPS610981DSER"))
    )
    (comp (ref "U5")
      (value "TPS61022RWUT")
      (footprint "RWU0007A")
      (description "8-A Boost Converter with 0.5-V Ultra-Low Input Voltage, RWU0007A (VQFN-HR-7)")
      (fields
        (field (name "ALTERNATE PARTNUMBER") "TPS61022RWUR")
        (field (name "MANUFACTURER") "Texas Instruments")
        (field (name "PARTNUMBER") "TPS61022RWUT")
      )
      (libsource (lib "Altium Vault - TI") (part "CMP-0078851-2"))
    )
  )
  (nets
    (net (code "1") (name "/3.3Vout") (class "Default")
      (node (ref "C12") (pin "1") (pinfunction "1_1") (pintype "passive"))
      (node (ref "C13") (pin "1") (pinfunction "1_1") (pintype "passive"))
      (node (ref "C23") (pin "1") (pinfunction "1_1") (pintype "passive"))
      (node (ref "C24") (pin "1") (pinfunction "1_1") (pintype "passive"))
      (node (ref "C25") (pin "1") (pinfunction "1_1") (pintype "passive"))
      (node (ref "C5") (pin "1") (pinfunction "1_1") (pintype "passive"))
      (node (ref "D2") (pin "1") (pinfunction "K_1") (pintype "passive"))
      (node (ref "Q2") (pin "1") (pinfunction "D_1") (pintype "passive"))
      (node (ref "Q2") (pin "2") (pinfunction "D_2") (pintype "passive"))
      (node (ref "Q2") (pin "5") (pinfunction "D_5") (pintype "passive"))
      (node (ref "Q2") (pin "6") (pinfunction "D_6") (pintype "passive"))
      (node (ref "Q2") (pin "8") (pinfunction "D_8") (pintype "passive"))
      (node (ref "R14") (pin "2") (pinfunction "2_2") (pintype "passive"))
      (node (ref "R18") (pin "2") (pinfunction "2_2") (pintype "passive"))
      (node (ref "R34") (pin "2") (pinfunction "2_2") (pintype "passive"))
      (node (ref "TP6") (pin "1") (pintype "passive"))
      (node (ref "U5") (pin "3") (pinfunction "VOUT_3") (pintype "power_in"))
    )
    (net (code "2") (name "/EN_U3") (class "Default")
      (node (ref "Q4") (pin "3") (pinfunction "C_3") (pintype "passive"))
      (node (ref "R29") (pin "1") (pinfunction "1_1") (pintype "passive"))
      (node (ref "R32") (pin "2") (pinfunction "2_2") (pintype "passive"))
      (node (ref "U5") (pin "5") (pinfunction "EN_5") (pintype "input"))
    )
    (net (code "3") (name "/FB1") (class "Default")
      (node (ref "C5") (pin "2") (pinfunction "2_2") (pintype "passive"))
      (node (ref "R18") (pin "1") (pinfunction "1_1") (pintype "passive"))
      (node (ref "R23") (pin "2") (pinfunction "2_2") (pintype "passive"))
      (node (ref "U2") (pin "5") (pinfunction "FB_5") (pintype "input"))
    )
    (net (code "4") (name "/V_backup") (class "Default")
      (node (ref "BT1") (pin "2") (pinfunction "-_2") (pintype "passive"))
      (node (ref "C11") (pin "1") (pinfunction "+_1") (pintype "passive"))
      (node (ref "C16") (pin "1") (pinfunction "1_1") (pintype "passive"))
      (node (ref "C19") (pin "1") (pinfunction "1_1") (pintype "passive"))
      (node (ref "C20") (pin "1") (pinfunction "1_1") (pintype "passive"))
      (node (ref "C22") (pin "1") (pinfunction "1_1") (pintype "passive"))
      (node (ref "L3") (pin "1") (pinfunction "1_1") (pintype "passive"))
      (node (ref "L4") (pin "1") (pinfunction "1_1") (pintype "passive"))
      (node (ref "Q1") (pin "1") (pinfunction "D_1") (pintype "passive"))
      (node (ref "Q1") (pin "2") (pinfunction "D_2") (pintype "passive"))
      (node (ref "Q1") (pin "3") (pinfunction "D_3") (pintype "passive"))
      (node (ref "R12") (pin "2") (pinfunction "2_2") (pintype "passive"))
      (node (ref "R26") (pin "1") (pinfunction "1_1") (pintype "passive"))
      (node (ref "R29") (pin "2") (pinfunction "2_2") (pintype "passive"))
      (node (ref "R30") (pin "2") (pinfunction "2_2") (pintype "passive"))
      (node (ref "R32") (pin "1") (pinfunction "1_1") (pintype "passive"))
      (node (ref "R9") (pin "2") (pinfunction "2_2") (pintype "passive"))
      (node (ref "TP5") (pin "1") (pintype "passive"))
      (node (ref "U5") (pin "7") (pinfunction "VIN_7") (pintype "power_in"))
    )
    (net (code "5") (name "/Vin") (class "Default")
      (node (ref "C101") (pin "1") (pinfunction "+_1") (pintype "passive"))
      (node (ref "C3") (pin "1") (pinfunction "1_1") (pintype "passive"))
      (node (ref "C4") (pin "1") (pinfunction "1_1") (pintype "passive"))
      (node (ref "C7") (pin "1") (pinfunction "1_1") (pintype "passive"))
      (node (ref "C8") (pin "1") (pinfunction "1_1") (pintype "passive"))
      (node (ref "D1") (pin "3") (pinfunction "K_3") (pintype "passive"))
      (node (ref "D4") (pin "3") (pinfunction "K_3") (pintype "passive"))
      (node (ref "D5") (pin "3") (pinfunction "K_3") (pintype "passive"))
      (node (ref "R1") (pin "1") (pinfunction "1_1") (pintype "passive"))
      (node (ref "R13") (pin "1") (pinfunction "1_1") (pintype "passive"))
      (node (ref "R16") (pin "2") (pinfunction "2_2") (pintype "passive"))
      (node (ref "R17") (pin "2") (pinfunction "2_2") (pintype "passive"))
      (node (ref "R3") (pin "1") (pinfunction "1_1") (pintype "passive"))
      (node (ref "R5") (pin "1") (pinfunction "1_1") (pintype "passive"))
      (node (ref "TP1") (pin "1") (pintype "passive"))
      (node (ref "U1") (pin "2") (pinfunction "VIN_2") (pintype "power_in"))
      (node (ref "U2") (pin "1") (pinfunction "VIN_1") (pintype "power_in"))
    )
    (net (code "6") (name "GND") (class "Default")
      (node (ref "BT1") (pin "1") (pinfunction "+_1") (pintype "passive"))
      (node (ref "C1") (pin "2") (pinfunction "2_2") (pintype "passive"))
      (node (ref "C10") (pin "2") (pinfunction "2_2") (pintype "passive"))
      (node (ref "C101") (pin "2") (pinfunction "-_2") (pintype "passive"))
      (node (ref "C11") (pin "2") (pinfunction "-_2") (pintype "passive"))
      (node (ref "C12") (pin "2") (pinfunction "2_2") (pintype "passive"))
      (node (ref "C13") (pin "2") (pinfunction "2_2") (pintype "passive"))
      (node (ref "C14") (pin "2") (pinfunction "2_2") (pintype "passive"))
      (node (ref "C15") (pin "2") (pinfunction "2_2") (pintype "passive"))
      (node (ref "C16") (pin "2") (pinfunction "2_2") (pintype "passive"))
      (node (ref "C17") (pin "2") (pinfunction "2_2") (pintype "passive"))
      (node (ref "C18") (pin "2") (pinfunction "2_2") (pintype "passive"))
      (node (ref "C19") (pin "2") (pinfunction "2_2") (pintype "passive"))
      (node (ref "C2") (pin "2") (pinfunction "2_2") (pintype "passive"))
      (node (ref "C20") (pin "2") (pinfunction "2_2") (pintype "passive"))
      (node (ref "C21") (pin "2") (pinfunction "2_2") (pintype "passive"))
      (node (ref "C22") (pin "2") (pinfunction "2_2") (pintype "passive"))
      (node (ref "C24") (pin "2") (pinfunction "2_2") (pintype "passive"))
      (node (ref "C25") (pin "2") (pinfunction "2_2") (pintype "passive"))
      (node (ref "C3") (pin "2") (pinfunction "2_2") (pintype "passive"))
      (node (ref "C4") (pin "2") (pinfunction "2_2") (pintype "passive"))
      (node (ref "C7") (pin "2") (pinfunction "2_2") (pintype "passive"))
      (node (ref "C8") (pin "2") (pinfunction "2_2") (pintype "passive"))
      (node (ref "C9") (pin "2") (pinfunction "2_2") (pintype "passive"))
      (node (ref "D3") (pin "2") (pinfunction "A_2") (pintype "passive"))
      (node (ref "Q4") (pin "2") (pinfunction "E_2") (pintype "passive"))
      (node (ref "R21") (pin "1") (pinfunction "1_1") (pintype "passive"))
      (node (ref "R22") (pin "1") (pinfunction "1_1") (pintype "passive"))
      (node (ref "R23") (pin "1") (pinfunction "1_1") (pintype "passive"))
      (node (ref "R24") (pin "1") (pinfunction "1_1") (pintype "passive"))
      (node (ref "R27") (pin "1") (pinfunction "1_1") (pintype "passive"))
      (node (ref "R28") (pin "2") (pinfunction "2_2") (pintype "passive"))
      (node (ref "R36") (pin "1") (pinfunction "1_1") (pintype "passive"))
      (node (ref "R37") (pin "1") (pinfunction "1_1") (pintype "passive"))
      (node (ref "R38") (pin "1") (pinfunction "1_1") (pintype "passive"))
      (node (ref "R7") (pin "1") (pinfunction "1_1") (pintype "passive"))
      (node (ref "TP3") (pin "1") (pintype "passive"))
      (node (ref "TP4") (pin "1") (pintype "passive"))
      (node (ref "TP7") (pin "1") (pintype "passive"))
      (node (ref "U1") (pin "1") (pinfunction "PGND_1") (pintype "power_in"))
      (node (ref "U1") (pin "4") (pinfunction "AGND_4") (pintype "power_in"))
      (node (ref "U1") (pin "5") (pinfunction "FB_5") (pintype "passive"))
      (node (ref "U1") (pin "9") (pinfunction "EP_9") (pintype "power_in"))
      (node (ref "U2") (pin "3") (pinfunction "GND_3") (pintype "power_in"))
      (node (ref "U2") (pin "4") (pinfunction "AGND_4") (pintype "power_in"))
      (node (ref "U3") (pin "3") (pinfunction "ANODE_3") (pintype "passive"))
      (node (ref "U4") (pin "6") (pinfunction "GND_6") (pintype "power_in"))
      (node (ref "U5") (pin "1") (pinfunction "GND_1") (pintype "power_in"))
    )
    (net (code "7") (name "Net-(D1-A)") (class "Default")
      (node (ref "D1") (pin "1") (pinfunction "A_1") (pintype "passive"))
      (node (ref "D1") (pin "2") (pinfunction "NC_2") (pintype "passive"))
      (node (ref "R4") (pin "1") (pinfunction "1_1") (pintype "passive"))
      (node (ref "R7") (pin "2") (pinfunction "2_2") (pintype "passive"))
    )
    (net (code "8") (name "Net-(D2-A)") (class "Default")
      (node (ref "C10") (pin "1") (pinfunction "1_1") (pintype "passive"))
      (node (ref "C9") (pin "1") (pinfunction "1_1") (pintype "passive"))
      (node (ref "D2") (pin "2") (pinfunction "A_2") (pintype "passive"))
      (node (ref "L2") (pin "2") (pinfunction "2_2") (pintype "passive"))
      (node (ref "Q2") (pin "4") (pinfunction "S_4") (pintype "passive"))
      (node (ref "Q2") (pin "7") (pinfunction "S_7") (pintype "passive"))
      (node (ref "R20") (pin "2") (pinfunction "2_2") (pintype "passive"))
    )
    (net (code "9") (name "Net-(D3-K)") (class "Default")
      (node (ref "D3") (pin "1") (pinfunction "K_1") (pintype "passive"))
      (node (ref "R11") (pin "1") (pinfunction "1_1") (pintype "passive"))
      (node (ref "R19") (pin "2") (pinfunction "2_2") (pintype "passive"))
      (node (ref "R9") (pin "1") (pinfunction "1_1") (pintype "passive"))
    )
    (net (code "10") (name "Net-(D4-A)") (class "Default")
      (node (ref "D4") (pin "1") (pinfunction "A_1") (pintype "passive"))
      (node (ref "R25") (pin "2") (pinfunction "2_2") (pintype "passive"))
    )
    (net (code "11") (name "Net-(D5-A)") (class "Default")
      (node (ref "D5") (pin "1") (pinfunction "A_1") (pintype "passive"))
      (node (ref "R33") (pin "2") (pinfunction "2_2") (pintype "passive"))
    )
    (net (code "12") (name "Net-(D6-A)") (class "Default")
      (node (ref "D6") (pin "1") (pinfunction "A_1") (pintype "passive"))
      (node (ref "R25") (pin "1") (pinfunction "1_1") (pintype "passive"))
      (node (ref "R27") (pin "2") (pinfunction "2_2") (pintype "passive"))
    )
    (net (code "13") (name "Net-(D6-K)") (class "Default")
      (node (ref "D6") (pin "3") (pinfunction "K_3") (pintype "passive"))
      (node (ref "R31") (pin "1") (pinfunction "1_1") (pintype "passive"))
    )
    (net (code "14") (name "Net-(Q1-G)") (class "Default")
      (node (ref "Q1") (pin "4") (pinfunction "G_4") (pintype "passive"))
      (node (ref "R10") (pin "1") (pinfunction "1_1") (pintype "passive"))
      (node (ref "R11") (pin "2") (pinfunction "2_2") (pintype "passive"))
    )
    (net (code "15") (name "Net-(Q1-S-Pad5)") (class "Default")
      (node (ref "Q1") (pin "5") (pinfunction "S_5") (pintype "passive"))
      (node (ref "Q1") (pin "6") (pinfunction "S_6") (pintype "passive"))
      (node (ref "Q1") (pin "7") (pinfunction "S_7") (pintype "passive"))
      (node (ref "Q1") (pin "8") (pinfunction "S_8") (pintype "passive"))
      (node (ref "Q1") (pin "9") (pinfunction "S_9") (pintype "passive"))
      (node (ref "R6") (pin "2") (pinfunction "2_2") (pintype "passive"))
      (node (ref "R8") (pin "2") (pinfunction "2_2") (pintype "passive"))
    )
    (net (code "16") (name "Net-(Q2-G)") (class "Default")
      (node (ref "Q2") (pin "3") (pinfunction "G_3") (pintype "passive"))
      (node (ref "R4") (pin "2") (pinfunction "2_2") (pintype "passive"))
    )
    (net (code "17") (name "Net-(Q3-B)") (class "Default")
      (node (ref "Q3") (pin "1") (pinfunction "B_1") (pintype "passive"))
      (node (ref "R10") (pin "2") (pinfunction "2_2") (pintype "passive"))
      (node (ref "R15") (pin "2") (pinfunction "2_2") (pintype "passive"))
      (node (ref "R8") (pin "1") (pinfunction "1_1") (pintype "passive"))
    )
    (net (code "18") (name "Net-(Q3-C)") (class "Default")
      (node (ref "Q3") (pin "3") (pinfunction "C_3") (pintype "passive"))
      (node (ref "R19") (pin "1") (pinfunction "1_1") (pintype "passive"))
    )
    (net (code "19") (name "Net-(Q3-E)") (class "Default")
      (node (ref "Q3") (pin "2") (pinfunction "E_2") (pintype "passive"))
      (node (ref "R3") (pin "2") (pinfunction "2_2") (pintype "passive"))
      (node (ref "R5") (pin "2") (pinfunction "2_2") (pintype "passive"))
      (node (ref "R6") (pin "1") (pinfunction "1_1") (pintype "passive"))
    )
    (net (code "20") (name "Net-(Q4-B)") (class "Default")
      (node (ref "Q4") (pin "1") (pinfunction "B_1") (pintype "passive"))
      (node (ref "R35") (pin "1") (pinfunction "1_1") (pintype "passive"))
    )
    (net (code "21") (name "Net-(R33-Pad1)") (class "Default")
      (node (ref "R33") (pin "1") (pinfunction "1_1") (pintype "passive"))
      (node (ref "R35") (pin "2") (pinfunction "2_2") (pintype "passive"))
      (node (ref "R36") (pin "2") (pinfunction "2_2") (pintype "passive"))
    )
    (net (code "22") (name "Net-(U1-EN)") (class "Default")
      (node (ref "R1") (pin "2") (pinfunction "2_2") (pintype "passive"))
      (node (ref "U1") (pin "3") (pinfunction "EN_3") (pintype "input"))
    )
    (net (code "23") (name "Net-(U1-PG)") (class "Default")
      (node (ref "R2") (pin "1") (pinfunction "1_1") (pintype "passive"))
      (node (ref "U1") (pin "8") (pinfunction "PG_8") (pintype "tri_state"))
    )
    (net (code "24") (name "Net-(U1-SW)") (class "Default")
      (node (ref "L1") (pin "1") (pinfunction "1_1") (pintype "passive"))
      (node (ref "U1") (pin "7") (pinfunction "SW_7") (pintype "power_in"))
    )
    (net (code "25") (name "Net-(U1-VOS)") (class "Default")
      (node (ref "C1") (pin "1") (pinfunction "1_1") (pintype "passive"))
      (node (ref "C2") (pin "1") (pinfunction "1_1") (pintype "passive"))
      (node (ref "L1") (pin "2") (pinfunction "2_2") (pintype "passive"))
      (node (ref "R2") (pin "2") (pinfunction "2_2") (pintype "passive"))
      (node (ref "TP2") (pin "1") (pintype "passive"))
      (node (ref "U1") (pin "6") (pinfunction "VOS_6") (pintype "input"))
    )
    (net (code "26") (name "Net-(U2-EN)") (class "Default")
      (node (ref "R13") (pin "2") (pinfunction "2_2") (pintype "passive"))
      (node (ref "U2") (pin "8") (pinfunction "EN_8") (pintype "input"))
    )
    (net (code "27") (name "Net-(U2-FSEL)") (class "Default")
      (node (ref "R17") (pin "1") (pinfunction "1_1") (pintype "passive"))
      (node (ref "R21") (pin "2") (pinfunction "2_2") (pintype "passive"))
      (node (ref "U2") (pin "11") (pinfunction "FSEL_11") (pintype "input"))
    )
    (net (code "28") (name "Net-(U2-MODE)") (class "Default")
      (node (ref "R16") (pin "1") (pinfunction "1_1") (pintype "passive"))
      (node (ref "R22") (pin "2") (pinfunction "2_2") (pintype "passive"))
      (node (ref "U2") (pin "10") (pinfunction "MODE_10") (pintype "input"))
    )
    (net (code "29") (name "Net-(U2-PG)") (class "Default")
      (node (ref "R20") (pin "1") (pinfunction "1_1") (pintype "passive"))
      (node (ref "U2") (pin "7") (pinfunction "PG_7") (pintype "open_collector"))
    )
    (net (code "30") (name "Net-(U2-SS{slash}TR)") (class "Default")
      (node (ref "C15") (pin "1") (pinfunction "1_1") (pintype "passive"))
      (node (ref "U2") (pin "9") (pinfunction "SS/TR_9") (pintype "input"))
    )
    (net (code "31") (name "Net-(U2-SW)") (class "Default")
      (node (ref "L2") (pin "1") (pinfunction "1_1") (pintype "passive"))
      (node (ref "U2") (pin "2") (pinfunction "SW_2") (pintype "power_in"))
    )
    (net (code "32") (name "Net-(U2-VOS)") (class "Default")
      (node (ref "R14") (pin "1") (pinfunction "1_1") (pintype "passive"))
      (node (ref "U2") (pin "6") (pinfunction "VOS_6") (pintype "input"))
    )
    (net (code "33") (name "Net-(U3-CATHODE)") (class "Default")
      (node (ref "C14") (pin "1") (pinfunction "1_1") (pintype "passive"))
      (node (ref "C6") (pin "2") (pinfunction "2_2") (pintype "passive"))
      (node (ref "R15") (pin "1") (pinfunction "1_1") (pintype "passive"))
      (node (ref "U3") (pin "1") (pinfunction "CATHODE_1") (pintype "passive"))
    )
    (net (code "34") (name "Net-(U3-REF)") (class "Default")
      (node (ref "C6") (pin "1") (pinfunction "1_1") (pintype "passive"))
      (node (ref "R12") (pin "1") (pinfunction "1_1") (pintype "passive"))
      (node (ref "R24") (pin "2") (pinfunction "2_2") (pintype "passive"))
      (node (ref "U3") (pin "2") (pinfunction "REF_2") (pintype "input"))
    )
    (net (code "35") (name "Net-(U4-MODE)") (class "Default")
      (node (ref "R28") (pin "1") (pinfunction "1_1") (pintype "passive"))
      (node (ref "U4") (pin "4") (pinfunction "MODE_4") (pintype "input"))
    )
    (net (code "36") (name "Net-(U4-SW)") (class "Default")
      (node (ref "L3") (pin "2") (pinfunction "2_2") (pintype "passive"))
      (node (ref "U4") (pin "2") (pinfunction "SW_2") (pintype "power_in"))
    )
    (net (code "37") (name "Net-(U4-VIN)") (class "Default")
      (node (ref "C17") (pin "1") (pinfunction "1_1") (pintype "passive"))
      (node (ref "R26") (pin "2") (pinfunction "2_2") (pintype "passive"))
      (node (ref "U4") (pin "3") (pinfunction "VIN_3") (pintype "power_in"))
    )
    (net (code "38") (name "Net-(U4-VMAIN)") (class "Default")
      (node (ref "C18") (pin "1") (pinfunction "1_1") (pintype "passive"))
      (node (ref "TP8") (pin "1") (pintype "passive"))
      (node (ref "U4") (pin "1") (pinfunction "VMAIN_1") (pintype "power_in"))
    )
    (net (code "39") (name "Net-(U4-VSUB)") (class "Default")
      (node (ref "C21") (pin "1") (pinfunction "1_1") (pintype "passive"))
      (node (ref "U4") (pin "5") (pinfunction "VSUB_5") (pintype "power_in"))
    )
    (net (code "40") (name "Net-(U5-FB)") (class "Default")
      (node (ref "C23") (pin "2") (pinfunction "2_2") (pintype "passive"))
      (node (ref "R31") (pin "2") (pinfunction "2_2") (pintype "passive"))
      (node (ref "R34") (pin "1") (pinfunction "1_1") (pintype "passive"))
      (node (ref "R38") (pin "2") (pinfunction "2_2") (pintype "passive"))
      (node (ref "U5") (pin "4") (pinfunction "FB_4") (pintype "input"))
    )
    (net (code "41") (name "Net-(U5-MODE)") (class "Default")
      (node (ref "R30") (pin "1") (pinfunction "1_1") (pintype "passive"))
      (node (ref "R37") (pin "2") (pinfunction "2_2") (pintype "passive"))
      (node (ref "U5") (pin "6") (pinfunction "MODE_6") (pintype "input"))
    )
    (net (code "42") (name "Net-(U5-SW)") (class "Default")
      (node (ref "L4") (pin "2") (pinfunction "2_2") (pintype "passive"))
      (node (ref "U5") (pin "2") (pinfunction "SW_2") (pintype "power_in"))
    )
    (net (code "43") (name "unconnected-(D4-NC-Pad2)") (class "Default")
      (node (ref "D4") (pin "2") (pinfunction "NC_2") (pintype "passive"))
    )
    (net (code "44") (name "unconnected-(D5-NC-Pad2)") (class "Default")
      (node (ref "D5") (pin "2") (pinfunction "NC_2") (pintype "passive"))
    )
  )
)
